# TheSchematic.net
KiCad netlist of a schematic drawn in EAGLE
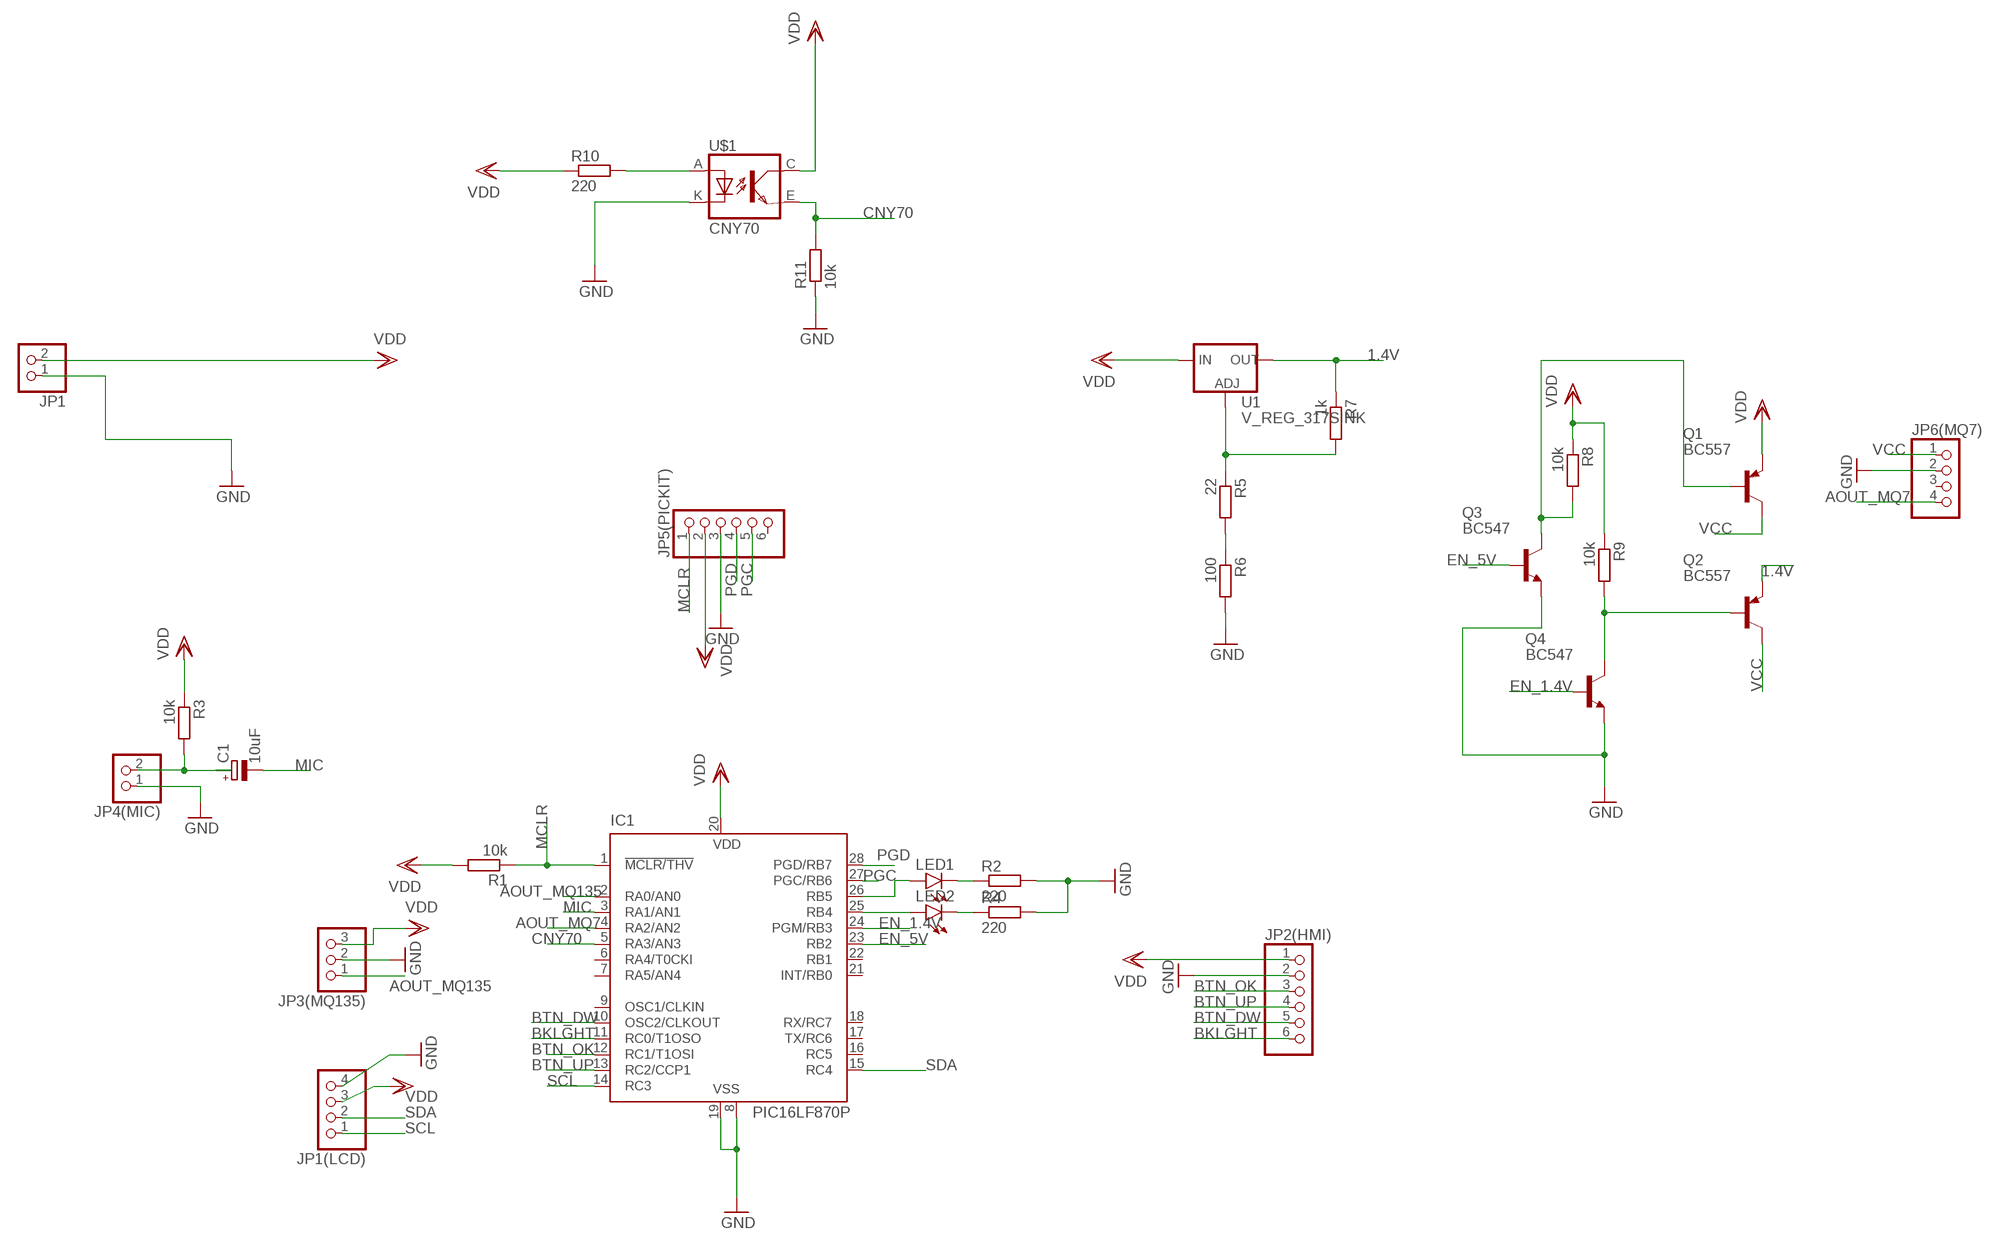
[diagram p0: schematic, sheet 1]

(export (version "E")
  (design (tool "Eeschema 10.0.6"))
  (components
    (comp (ref "C1")
      (value "10uF")
      (footprint "eagle-import:E1,8-4")
      (libsource (lib "eagle-import") (part "CPOL-EUE1.8-4"))
    )
    (comp (ref "IC1")
      (value "PIC16LF870P")
      (footprint "eagle-import:DIL28-3")
      (fields (field (name "MF") "MICROCHIP") (field (name "MPN") "PIC16LF870-I/SP"))
      (libsource (lib "eagle-import") (part "PIC16870PLF"))
    )
    (comp (ref "JP1")
      (value "PINHD-1X2")
      (footprint "eagle-import:1X02")
      (libsource (lib "eagle-import") (part "PINHD-1X2"))
    )
    (comp (ref "JP1(LCD)")
      (value "PINHD-1X4")
      (footprint "eagle-import:1X04")
      (libsource (lib "eagle-import") (part "PINHD-1X4"))
    )
    (comp (ref "JP2(HMI)")
      (value "PINHD-1X6")
      (footprint "eagle-import:1X06")
      (libsource (lib "eagle-import") (part "PINHD-1X6"))
    )
    (comp (ref "JP3(MQ135)")
      (value "PINHD-1X3")
      (footprint "eagle-import:1X03")
      (libsource (lib "eagle-import") (part "PINHD-1X3"))
    )
    (comp (ref "JP4(MIC)")
      (value "PINHD-1X2")
      (footprint "eagle-import:1X02")
      (libsource (lib "eagle-import") (part "PINHD-1X2"))
    )
    (comp (ref "JP5(PICKIT)")
      (value "PINHD-1X6")
      (footprint "eagle-import:1X06")
      (libsource (lib "eagle-import") (part "PINHD-1X6"))
    )
    (comp (ref "JP6(MQ7)")
      (value "PINHD-1X4")
      (footprint "eagle-import:1X04")
      (libsource (lib "eagle-import") (part "PINHD-1X4"))
    )
    (comp (ref "LED1")
      (value "LED5MM")
      (footprint "eagle-import:LED5MM")
      (libsource (lib "eagle-import") (part "LED5MM"))
    )
    (comp (ref "LED2")
      (value "LED5MM")
      (footprint "eagle-import:LED5MM")
      (libsource (lib "eagle-import") (part "LED5MM"))
    )
    (comp (ref "Q1")
      (value "BC557")
      (footprint "eagle-import:TO92-EBC")
      (libsource (lib "eagle-import") (part "BC557"))
    )
    (comp (ref "Q2")
      (value "BC557")
      (footprint "eagle-import:TO92-EBC")
      (libsource (lib "eagle-import") (part "BC557"))
    )
    (comp (ref "Q3")
      (value "BC547")
      (footprint "eagle-import:TO92")
      (libsource (lib "eagle-import") (part "BC547"))
    )
    (comp (ref "Q4")
      (value "BC547")
      (footprint "eagle-import:TO92")
      (libsource (lib "eagle-import") (part "BC547"))
    )
    (comp (ref "R1")
      (value "10k")
      (footprint "eagle-import:0204_7")
      (libsource (lib "eagle-import") (part "R-EU_0204/7"))
    )
    (comp (ref "R2")
      (value "220")
      (footprint "eagle-import:0207_10")
      (libsource (lib "eagle-import") (part "R-EU_0207/10"))
    )
    (comp (ref "R3")
      (value "10k")
      (footprint "eagle-import:0204_7")
      (libsource (lib "eagle-import") (part "R-EU_0204/7"))
    )
    (comp (ref "R4")
      (value "220")
      (footprint "eagle-import:0207_10")
      (libsource (lib "eagle-import") (part "R-EU_0207/10"))
    )
    (comp (ref "R5")
      (value "22")
      (footprint "eagle-import:0204_7")
      (libsource (lib "eagle-import") (part "R-EU_0204/7"))
    )
    (comp (ref "R6")
      (value "100")
      (footprint "eagle-import:0204_7")
      (libsource (lib "eagle-import") (part "R-EU_0204/7"))
    )
    (comp (ref "R7")
      (value "1k")
      (footprint "eagle-import:0204_7")
      (libsource (lib "eagle-import") (part "R-EU_0204/7"))
    )
    (comp (ref "R8")
      (value "10k")
      (footprint "eagle-import:0204_7")
      (libsource (lib "eagle-import") (part "R-EU_0204/7"))
    )
    (comp (ref "R9")
      (value "10k")
      (footprint "eagle-import:0204_7")
      (libsource (lib "eagle-import") (part "R-EU_0204/7"))
    )
    (comp (ref "R10")
      (value "220")
      (footprint "eagle-import:0207_10")
      (libsource (lib "eagle-import") (part "R-EU_0207/10"))
    )
    (comp (ref "R11")
      (value "10k")
      (footprint "eagle-import:0207_10")
      (libsource (lib "eagle-import") (part "R-EU_0207/10"))
    )
    (comp (ref "U$1")
      (value "CNY70")
      (footprint "eagle-import:4")
      (libsource (lib "eagle-import") (part "CNY70"))
    )
    (comp (ref "U1")
      (value "V_REG_317SINK")
      (footprint "eagle-import:TO220-ADJ")
      (libsource (lib "eagle-import") (part "V_REG_317SINK"))
    )
  )
  (nets
    (net (code "1") (name "/1.4V") (class "Default")
      (node (ref "Q2") (pin "E") (pinfunction "E_E") (pintype "passive"))
      (node (ref "R7") (pin "1") (pinfunction "1_1") (pintype "passive"))
      (node (ref "U1") (pin "OUT") (pinfunction "OUT_OUT") (pintype "output"))
    )
    (net (code "2") (name "/AOUT_MQ7") (class "Default")
      (node (ref "IC1") (pin "4") (pinfunction "RA2/AN2_4") (pintype "bidirectional"))
      (node (ref "JP6(MQ7)") (pin "4") (pinfunction "4_4") (pintype "passive"))
    )
    (net (code "3") (name "/AOUT_MQ135") (class "Default")
      (node (ref "IC1") (pin "2") (pinfunction "RA0/AN0_2") (pintype "bidirectional"))
      (node (ref "JP3(MQ135)") (pin "1") (pinfunction "1_1") (pintype "passive"))
    )
    (net (code "4") (name "/BKLGHT") (class "Default")
      (node (ref "IC1") (pin "11") (pinfunction "RC0/T1OSO_11") (pintype "bidirectional"))
      (node (ref "JP2(HMI)") (pin "6") (pinfunction "6_6") (pintype "passive"))
    )
    (net (code "5") (name "/BTN_DW") (class "Default")
      (node (ref "IC1") (pin "10") (pinfunction "OSC2/CLKOUT_10") (pintype "output"))
      (node (ref "JP2(HMI)") (pin "5") (pinfunction "5_5") (pintype "passive"))
    )
    (net (code "6") (name "/BTN_OK") (class "Default")
      (node (ref "IC1") (pin "12") (pinfunction "RC1/T1OSI_12") (pintype "bidirectional"))
      (node (ref "JP2(HMI)") (pin "3") (pinfunction "3_3") (pintype "passive"))
    )
    (net (code "7") (name "/BTN_UP") (class "Default")
      (node (ref "IC1") (pin "13") (pinfunction "RC2/CCP1_13") (pintype "bidirectional"))
      (node (ref "JP2(HMI)") (pin "4") (pinfunction "4_4") (pintype "passive"))
    )
    (net (code "8") (name "/CNY70") (class "Default")
      (node (ref "IC1") (pin "5") (pinfunction "RA3/AN3_5") (pintype "bidirectional"))
      (node (ref "R11") (pin "2") (pinfunction "2_2") (pintype "passive"))
      (node (ref "U$1") (pin "E") (pinfunction "EMI_E") (pintype "passive"))
    )
    (net (code "9") (name "/EN_1.4V") (class "Default")
      (node (ref "IC1") (pin "24") (pinfunction "PGM/RB3_24") (pintype "bidirectional"))
      (node (ref "Q4") (pin "2") (pinfunction "B_2") (pintype "passive"))
    )
    (net (code "10") (name "/EN_5V") (class "Default")
      (node (ref "IC1") (pin "23") (pinfunction "RB2_23") (pintype "bidirectional"))
      (node (ref "Q3") (pin "2") (pinfunction "B_2") (pintype "passive"))
    )
    (net (code "11") (name "/MCLR") (class "Default")
      (node (ref "IC1") (pin "1") (pinfunction "~{MCLR/THV}_1") (pintype "input"))
      (node (ref "JP5(PICKIT)") (pin "1") (pinfunction "1_1") (pintype "passive"))
      (node (ref "R1") (pin "1") (pinfunction "1_1") (pintype "passive"))
    )
    (net (code "12") (name "/MIC") (class "Default")
      (node (ref "C1") (pin "-") (pinfunction "-_-") (pintype "passive"))
      (node (ref "IC1") (pin "3") (pinfunction "RA1/AN1_3") (pintype "bidirectional"))
    )
    (net (code "13") (name "/PGC") (class "Default")
      (node (ref "IC1") (pin "27") (pinfunction "PGC/RB6_27") (pintype "bidirectional"))
      (node (ref "JP5(PICKIT)") (pin "5") (pinfunction "5_5") (pintype "passive"))
    )
    (net (code "14") (name "/PGD") (class "Default")
      (node (ref "IC1") (pin "28") (pinfunction "PGD/RB7_28") (pintype "bidirectional"))
      (node (ref "JP5(PICKIT)") (pin "4") (pinfunction "4_4") (pintype "passive"))
    )
    (net (code "15") (name "/SCL") (class "Default")
      (node (ref "IC1") (pin "14") (pinfunction "RC3_14") (pintype "bidirectional"))
      (node (ref "JP1(LCD)") (pin "1") (pinfunction "1_1") (pintype "passive"))
    )
    (net (code "16") (name "/SDA") (class "Default")
      (node (ref "IC1") (pin "15") (pinfunction "RC4_15") (pintype "bidirectional"))
      (node (ref "JP1(LCD)") (pin "2") (pinfunction "2_2") (pintype "passive"))
    )
    (net (code "17") (name "/VCC") (class "Default")
      (node (ref "JP6(MQ7)") (pin "1") (pinfunction "1_1") (pintype "passive"))
      (node (ref "Q1") (pin "C") (pinfunction "C_C") (pintype "passive"))
      (node (ref "Q2") (pin "C") (pinfunction "C_C") (pintype "passive"))
    )
    (net (code "18") (name "GND") (class "Default")
      (node (ref "IC1") (pin "19") (pinfunction "VSS_19") (pintype "power_in"))
      (node (ref "IC1") (pin "8") (pinfunction "VSS_8") (pintype "power_in"))
      (node (ref "JP1") (pin "1") (pinfunction "1_1") (pintype "passive"))
      (node (ref "JP1(LCD)") (pin "4") (pinfunction "4_4") (pintype "passive"))
      (node (ref "JP2(HMI)") (pin "2") (pinfunction "2_2") (pintype "passive"))
      (node (ref "JP3(MQ135)") (pin "2") (pinfunction "2_2") (pintype "passive"))
      (node (ref "JP4(MIC)") (pin "1") (pinfunction "1_1") (pintype "passive"))
      (node (ref "JP5(PICKIT)") (pin "3") (pinfunction "3_3") (pintype "passive"))
      (node (ref "JP6(MQ7)") (pin "2") (pinfunction "2_2") (pintype "passive"))
      (node (ref "Q3") (pin "1") (pinfunction "E_1") (pintype "passive"))
      (node (ref "Q4") (pin "1") (pinfunction "E_1") (pintype "passive"))
      (node (ref "R11") (pin "1") (pinfunction "1_1") (pintype "passive"))
      (node (ref "R2") (pin "2") (pinfunction "2_2") (pintype "passive"))
      (node (ref "R4") (pin "2") (pinfunction "2_2") (pintype "passive"))
      (node (ref "R6") (pin "2") (pinfunction "2_2") (pintype "passive"))
      (node (ref "U$1") (pin "K") (pinfunction "C_K") (pintype "passive"))
    )
    (net (code "19") (name "Net-(C1-Pad+)") (class "Default")
      (node (ref "C1") (pin "+") (pinfunction "+_+") (pintype "passive"))
      (node (ref "JP4(MIC)") (pin "2") (pinfunction "2_2") (pintype "passive"))
      (node (ref "R3") (pin "2") (pinfunction "2_2") (pintype "passive"))
    )
    (net (code "20") (name "Net-(IC1-RB4)") (class "Default")
      (node (ref "IC1") (pin "25") (pinfunction "RB4_25") (pintype "bidirectional"))
      (node (ref "LED2") (pin "A") (pinfunction "A_A") (pintype "passive"))
    )
    (net (code "21") (name "Net-(IC1-RB5)") (class "Default")
      (node (ref "IC1") (pin "26") (pinfunction "RB5_26") (pintype "bidirectional"))
      (node (ref "LED1") (pin "A") (pinfunction "A_A") (pintype "passive"))
    )
    (net (code "22") (name "Net-(LED1-C)") (class "Default")
      (node (ref "LED1") (pin "K") (pinfunction "C_K") (pintype "passive"))
      (node (ref "R2") (pin "1") (pinfunction "1_1") (pintype "passive"))
    )
    (net (code "23") (name "Net-(LED2-C)") (class "Default")
      (node (ref "LED2") (pin "K") (pinfunction "C_K") (pintype "passive"))
      (node (ref "R4") (pin "1") (pinfunction "1_1") (pintype "passive"))
    )
    (net (code "24") (name "Net-(Q3-C)") (class "Default")
      (node (ref "Q1") (pin "B") (pinfunction "B_B") (pintype "passive"))
      (node (ref "Q3") (pin "3") (pinfunction "C_3") (pintype "passive"))
      (node (ref "R8") (pin "2") (pinfunction "2_2") (pintype "passive"))
    )
    (net (code "25") (name "Net-(Q4-C)") (class "Default")
      (node (ref "Q2") (pin "B") (pinfunction "B_B") (pintype "passive"))
      (node (ref "Q4") (pin "3") (pinfunction "C_3") (pintype "passive"))
      (node (ref "R9") (pin "2") (pinfunction "2_2") (pintype "passive"))
    )
    (net (code "26") (name "Net-(R5-Pad1)") (class "Default")
      (node (ref "R5") (pin "1") (pinfunction "1_1") (pintype "passive"))
      (node (ref "R7") (pin "2") (pinfunction "2_2") (pintype "passive"))
      (node (ref "U1") (pin "ADJ") (pinfunction "ADJ_ADJ") (pintype "input"))
    )
    (net (code "27") (name "Net-(R5-Pad2)") (class "Default")
      (node (ref "R5") (pin "2") (pinfunction "2_2") (pintype "passive"))
      (node (ref "R6") (pin "1") (pinfunction "1_1") (pintype "passive"))
    )
    (net (code "28") (name "Net-(R10-Pad2)") (class "Default")
      (node (ref "R10") (pin "2") (pinfunction "2_2") (pintype "passive"))
      (node (ref "U$1") (pin "A") (pinfunction "A_A") (pintype "passive"))
    )
    (net (code "29") (name "VDD") (class "Default")
      (node (ref "IC1") (pin "20") (pinfunction "VDD_20") (pintype "power_in"))
      (node (ref "JP1") (pin "2") (pinfunction "2_2") (pintype "passive"))
      (node (ref "JP1(LCD)") (pin "3") (pinfunction "3_3") (pintype "passive"))
      (node (ref "JP2(HMI)") (pin "1") (pinfunction "1_1") (pintype "passive"))
      (node (ref "JP3(MQ135)") (pin "3") (pinfunction "3_3") (pintype "passive"))
      (node (ref "JP5(PICKIT)") (pin "2") (pinfunction "2_2") (pintype "passive"))
      (node (ref "Q1") (pin "E") (pinfunction "E_E") (pintype "passive"))
      (node (ref "R1") (pin "2") (pinfunction "2_2") (pintype "passive"))
      (node (ref "R10") (pin "1") (pinfunction "1_1") (pintype "passive"))
      (node (ref "R3") (pin "1") (pinfunction "1_1") (pintype "passive"))
      (node (ref "R8") (pin "1") (pinfunction "1_1") (pintype "passive"))
      (node (ref "R9") (pin "1") (pinfunction "1_1") (pintype "passive"))
      (node (ref "U$1") (pin "C") (pinfunction "COL_C") (pintype "passive"))
      (node (ref "U1") (pin "IN") (pinfunction "IN_IN") (pintype "input"))
    )
    (net (code "30") (name "unconnected-(IC1-INT{slash}RB0-Pad21)") (class "Default")
      (node (ref "IC1") (pin "21") (pinfunction "INT/RB0_21") (pintype "bidirectional"))
    )
    (net (code "31") (name "unconnected-(IC1-OSC1{slash}CLKIN-Pad9)") (class "Default")
      (node (ref "IC1") (pin "9") (pinfunction "OSC1/CLKIN_9") (pintype "input"))
    )
    (net (code "32") (name "unconnected-(IC1-RA4{slash}T0CKI-Pad6)") (class "Default")
      (node (ref "IC1") (pin "6") (pinfunction "RA4/T0CKI_6") (pintype "bidirectional"))
    )
    (net (code "33") (name "unconnected-(IC1-RA5{slash}AN4-Pad7)") (class "Default")
      (node (ref "IC1") (pin "7") (pinfunction "RA5/AN4_7") (pintype "bidirectional"))
    )
    (net (code "34") (name "unconnected-(IC1-RB1-Pad22)") (class "Default")
      (node (ref "IC1") (pin "22") (pinfunction "RB1_22") (pintype "bidirectional"))
    )
    (net (code "35") (name "unconnected-(IC1-RC5-Pad16)") (class "Default")
      (node (ref "IC1") (pin "16") (pinfunction "RC5_16") (pintype "bidirectional"))
    )
    (net (code "36") (name "unconnected-(IC1-RX{slash}RC7-Pad18)") (class "Default")
      (node (ref "IC1") (pin "18") (pinfunction "RX/RC7_18") (pintype "bidirectional"))
    )
    (net (code "37") (name "unconnected-(IC1-TX{slash}RC6-Pad17)") (class "Default")
      (node (ref "IC1") (pin "17") (pinfunction "TX/RC6_17") (pintype "bidirectional"))
    )
    (net (code "38") (name "unconnected-(JP5(PICKIT)-Pad6)") (class "Default")
      (node (ref "JP5(PICKIT)") (pin "6") (pinfunction "6_6") (pintype "passive"))
    )
    (net (code "39") (name "unconnected-(JP6(MQ7)-Pad3)") (class "Default")
      (node (ref "JP6(MQ7)") (pin "3") (pinfunction "3_3") (pintype "passive"))
    )
  )
)
